# Wemos_MHZ19.net
KiCad netlist of a schematic drawn in EAGLE
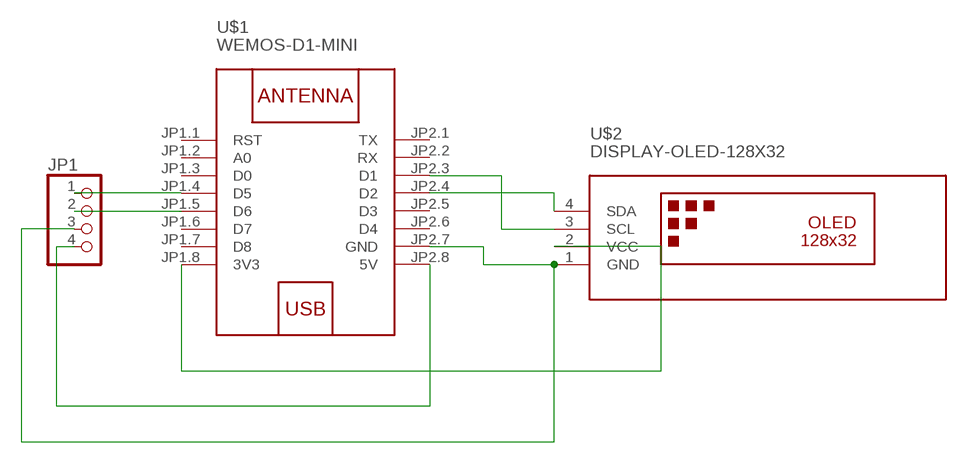
[diagram p0: schematic, sheet 1]

(export (version "E")
  (design (tool "Eeschema 10.0.6"))
  (components
    (comp (ref "JP1")
      (value "PINHD-1X4/90")
      (footprint "eagle-import:1X04_90")
      (libsource (lib "eagle-import") (part "PINHD-1X4/90"))
    )
    (comp (ref "U$1")
      (value "WEMOS-D1-MINI")
      (footprint "eagle-import:WEMOS-D1-MINI")
      (libsource (lib "eagle-import") (part "WEMOS-D1-MINI"))
    )
    (comp (ref "U$2")
      (value "DISPLAY-OLED-128X32")
      (footprint "eagle-import:DISPLAY-OLED-128X32")
      (libsource (lib "eagle-import") (part "DISPLAY-OLED-128X32"))
    )
  )
  (nets
    (net (code "1") (name "Net-(U$1-3V3)") (class "Default")
      (node (ref "U$1") (pin "JP1.8") (pinfunction "3V3_JP1.8") (pintype "power_in"))
      (node (ref "U$2") (pin "2") (pinfunction "VCC_2") (pintype "power_in"))
    )
    (net (code "2") (name "Net-(U$1-5V)") (class "Default")
      (node (ref "JP1") (pin "4") (pinfunction "4_4") (pintype "passive"))
      (node (ref "U$1") (pin "JP2.8") (pinfunction "5V_JP2.8") (pintype "power_in"))
    )
    (net (code "3") (name "Net-(U$1-D1)") (class "Default")
      (node (ref "U$1") (pin "JP2.3") (pinfunction "D1_JP2.3") (pintype "bidirectional"))
      (node (ref "U$2") (pin "3") (pinfunction "SCL_3") (pintype "bidirectional"))
    )
    (net (code "4") (name "Net-(U$1-D2)") (class "Default")
      (node (ref "U$1") (pin "JP2.4") (pinfunction "D2_JP2.4") (pintype "bidirectional"))
      (node (ref "U$2") (pin "4") (pinfunction "SDA_4") (pintype "bidirectional"))
    )
    (net (code "5") (name "Net-(U$1-D5)") (class "Default")
      (node (ref "JP1") (pin "1") (pinfunction "1_1") (pintype "passive"))
      (node (ref "U$1") (pin "JP1.4") (pinfunction "D5_JP1.4") (pintype "bidirectional"))
    )
    (net (code "6") (name "Net-(U$1-D6)") (class "Default")
      (node (ref "JP1") (pin "2") (pinfunction "2_2") (pintype "passive"))
      (node (ref "U$1") (pin "JP1.5") (pinfunction "D6_JP1.5") (pintype "bidirectional"))
    )
    (net (code "7") (name "Net-(U$1-GND)") (class "Default")
      (node (ref "JP1") (pin "3") (pinfunction "3_3") (pintype "passive"))
      (node (ref "U$1") (pin "JP2.7") (pinfunction "GND_JP2.7") (pintype "power_in"))
      (node (ref "U$2") (pin "1") (pinfunction "GND_1") (pintype "power_in"))
    )
    (net (code "8") (name "unconnected-(U$1-A0-PadJP1.2)") (class "Default")
      (node (ref "U$1") (pin "JP1.2") (pinfunction "A0_JP1.2") (pintype "bidirectional"))
    )
    (net (code "9") (name "unconnected-(U$1-D0-PadJP1.3)") (class "Default")
      (node (ref "U$1") (pin "JP1.3") (pinfunction "D0_JP1.3") (pintype "bidirectional"))
    )
    (net (code "10") (name "unconnected-(U$1-D3-PadJP2.5)") (class "Default")
      (node (ref "U$1") (pin "JP2.5") (pinfunction "D3_JP2.5") (pintype "bidirectional"))
    )
    (net (code "11") (name "unconnected-(U$1-D4-PadJP2.6)") (class "Default")
      (node (ref "U$1") (pin "JP2.6") (pinfunction "D4_JP2.6") (pintype "bidirectional"))
    )
    (net (code "12") (name "unconnected-(U$1-D7-PadJP1.6)") (class "Default")
      (node (ref "U$1") (pin "JP1.6") (pinfunction "D7_JP1.6") (pintype "bidirectional"))
    )
    (net (code "13") (name "unconnected-(U$1-D8-PadJP1.7)") (class "Default")
      (node (ref "U$1") (pin "JP1.7") (pinfunction "D8_JP1.7") (pintype "bidirectional"))
    )
    (net (code "14") (name "unconnected-(U$1-RST-PadJP1.1)") (class "Default")
      (node (ref "U$1") (pin "JP1.1") (pinfunction "RST_JP1.1") (pintype "bidirectional"))
    )
    (net (code "15") (name "unconnected-(U$1-RX-PadJP2.2)") (class "Default")
      (node (ref "U$1") (pin "JP2.2") (pinfunction "RX_JP2.2") (pintype "bidirectional"))
    )
    (net (code "16") (name "unconnected-(U$1-TX-PadJP2.1)") (class "Default")
      (node (ref "U$1") (pin "JP2.1") (pinfunction "TX_JP2.1") (pintype "bidirectional"))
    )
  )
)
